# SCH_PoC_Sensor_Jao.net
KiCad netlist of a schematic drawn in EasyEDA
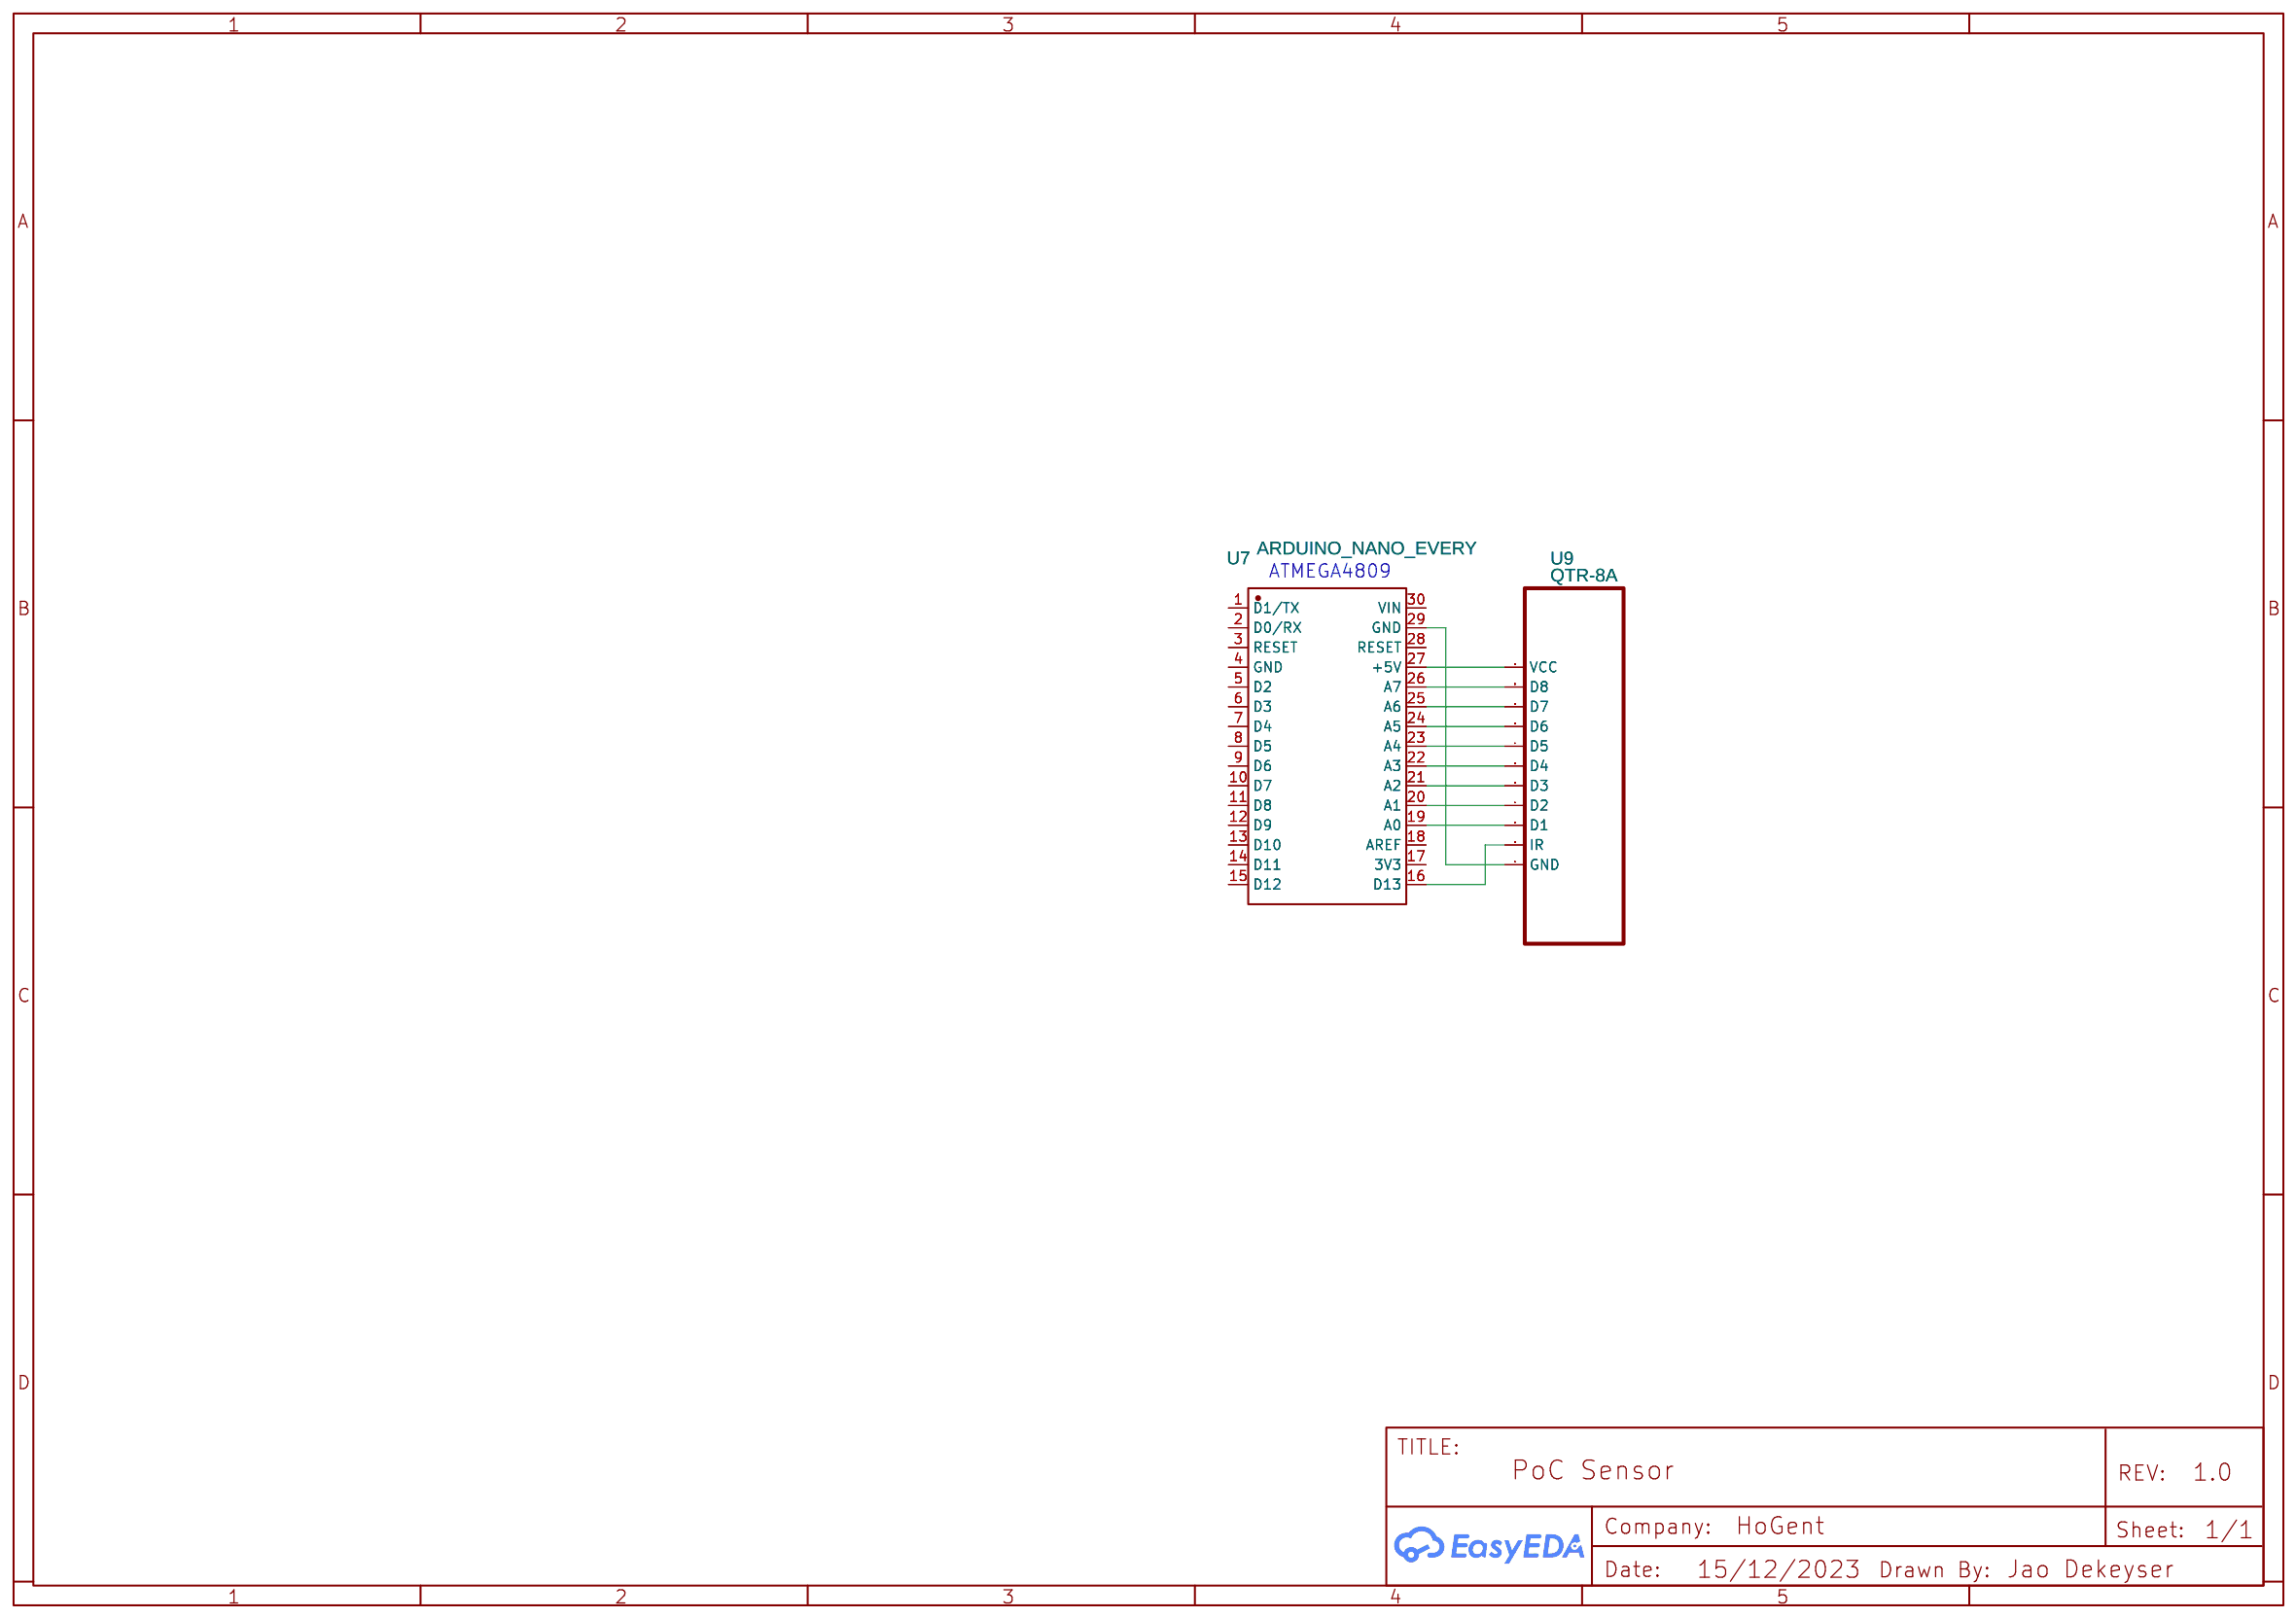
[diagram p0: schematic sheet]

(export (version "E")
  (design (tool "Eeschema 10.0.6"))
  (components
    (comp (ref "U7")
      (value "ARDUINO_NANO_EVERY")
      (fields (field (name "Manufacturer Part") "ARDUINO_NANO"))
      (libsource (lib "") (part "ARDUINO_NANO"))
    )
    (comp (ref "U9") (value "QTR-8A") (libsource (lib "") (part "QTR-8A")))
  )
  (nets
    (net (code "1") (name "Net-(U7-+5V)") (class "Default")
      (node (ref "U7") (pin "27") (pinfunction "+5V_27") (pintype "unspecified"))
      (node (ref "U9") (pin "11") (pinfunction "VCC_11") (pintype "unspecified"))
    )
    (net (code "2") (name "Net-(U7-A0)") (class "Default")
      (node (ref "U7") (pin "19") (pinfunction "A0_19") (pintype "unspecified"))
      (node (ref "U9") (pin "3") (pinfunction "D1_3") (pintype "unspecified"))
    )
    (net (code "3") (name "Net-(U7-A1)") (class "Default")
      (node (ref "U7") (pin "20") (pinfunction "A1_20") (pintype "unspecified"))
      (node (ref "U9") (pin "4") (pinfunction "D2_4") (pintype "unspecified"))
    )
    (net (code "4") (name "Net-(U7-A2)") (class "Default")
      (node (ref "U7") (pin "21") (pinfunction "A2_21") (pintype "unspecified"))
      (node (ref "U9") (pin "5") (pinfunction "D3_5") (pintype "unspecified"))
    )
    (net (code "5") (name "Net-(U7-A3)") (class "Default")
      (node (ref "U7") (pin "22") (pinfunction "A3_22") (pintype "unspecified"))
      (node (ref "U9") (pin "6") (pinfunction "D4_6") (pintype "unspecified"))
    )
    (net (code "6") (name "Net-(U7-A4)") (class "Default")
      (node (ref "U7") (pin "23") (pinfunction "A4_23") (pintype "unspecified"))
      (node (ref "U9") (pin "7") (pinfunction "D5_7") (pintype "unspecified"))
    )
    (net (code "7") (name "Net-(U7-A5)") (class "Default")
      (node (ref "U7") (pin "24") (pinfunction "A5_24") (pintype "unspecified"))
      (node (ref "U9") (pin "8") (pinfunction "D6_8") (pintype "unspecified"))
    )
    (net (code "8") (name "Net-(U7-A6)") (class "Default")
      (node (ref "U7") (pin "25") (pinfunction "A6_25") (pintype "unspecified"))
      (node (ref "U9") (pin "9") (pinfunction "D7_9") (pintype "unspecified"))
    )
    (net (code "9") (name "Net-(U7-A7)") (class "Default")
      (node (ref "U7") (pin "26") (pinfunction "A7_26") (pintype "unspecified"))
      (node (ref "U9") (pin "10") (pinfunction "D8_10") (pintype "unspecified"))
    )
    (net (code "10") (name "Net-(U7-D13)") (class "Default")
      (node (ref "U7") (pin "16") (pinfunction "D13_16") (pintype "unspecified"))
      (node (ref "U9") (pin "2") (pinfunction "IR_2") (pintype "unspecified"))
    )
    (net (code "11") (name "Net-(U9-GND)") (class "Default")
      (node (ref "U7") (pin "29") (pinfunction "GND_29") (pintype "unspecified"))
      (node (ref "U9") (pin "1") (pinfunction "GND_1") (pintype "unspecified"))
    )
    (net (code "12") (name "unconnected-(U7-3V3-Pad17)") (class "Default")
      (node (ref "U7") (pin "17") (pinfunction "3V3_17") (pintype "unspecified"))
    )
    (net (code "13") (name "unconnected-(U7-AREF-Pad18)") (class "Default")
      (node (ref "U7") (pin "18") (pinfunction "AREF_18") (pintype "unspecified"))
    )
    (net (code "14") (name "unconnected-(U7-D0{slash}RX-Pad2)") (class "Default")
      (node (ref "U7") (pin "2") (pinfunction "D0/RX_2") (pintype "unspecified"))
    )
    (net (code "15") (name "unconnected-(U7-D1{slash}TX-Pad1)") (class "Default")
      (node (ref "U7") (pin "1") (pinfunction "D1/TX_1") (pintype "unspecified"))
    )
    (net (code "16") (name "unconnected-(U7-D2-Pad5)") (class "Default")
      (node (ref "U7") (pin "5") (pinfunction "D2_5") (pintype "unspecified"))
    )
    (net (code "17") (name "unconnected-(U7-D3-Pad6)") (class "Default")
      (node (ref "U7") (pin "6") (pinfunction "D3_6") (pintype "unspecified"))
    )
    (net (code "18") (name "unconnected-(U7-D4-Pad7)") (class "Default")
      (node (ref "U7") (pin "7") (pinfunction "D4_7") (pintype "unspecified"))
    )
    (net (code "19") (name "unconnected-(U7-D5-Pad8)") (class "Default")
      (node (ref "U7") (pin "8") (pinfunction "D5_8") (pintype "unspecified"))
    )
    (net (code "20") (name "unconnected-(U7-D6-Pad9)") (class "Default")
      (node (ref "U7") (pin "9") (pinfunction "D6_9") (pintype "unspecified"))
    )
    (net (code "21") (name "unconnected-(U7-D7-Pad10)") (class "Default")
      (node (ref "U7") (pin "10") (pinfunction "D7_10") (pintype "unspecified"))
    )
    (net (code "22") (name "unconnected-(U7-D8-Pad11)") (class "Default")
      (node (ref "U7") (pin "11") (pinfunction "D8_11") (pintype "unspecified"))
    )
    (net (code "23") (name "unconnected-(U7-D9-Pad12)") (class "Default")
      (node (ref "U7") (pin "12") (pinfunction "D9_12") (pintype "unspecified"))
    )
    (net (code "24") (name "unconnected-(U7-D10-Pad13)") (class "Default")
      (node (ref "U7") (pin "13") (pinfunction "D10_13") (pintype "unspecified"))
    )
    (net (code "25") (name "unconnected-(U7-D11-Pad14)") (class "Default")
      (node (ref "U7") (pin "14") (pinfunction "D11_14") (pintype "unspecified"))
    )
    (net (code "26") (name "unconnected-(U7-D12-Pad15)") (class "Default")
      (node (ref "U7") (pin "15") (pinfunction "D12_15") (pintype "unspecified"))
    )
    (net (code "27") (name "unconnected-(U7-GND-Pad4)") (class "Default")
      (node (ref "U7") (pin "4") (pinfunction "GND_4") (pintype "unspecified"))
    )
    (net (code "28") (name "unconnected-(U7-RESET-Pad3)") (class "Default")
      (node (ref "U7") (pin "3") (pinfunction "RESET_3") (pintype "unspecified"))
    )
    (net (code "29") (name "unconnected-(U7-RESET-Pad28)") (class "Default")
      (node (ref "U7") (pin "28") (pinfunction "RESET_28") (pintype "unspecified"))
    )
    (net (code "30") (name "unconnected-(U7-VIN-Pad30)") (class "Default")
      (node (ref "U7") (pin "30") (pinfunction "VIN_30") (pintype "unspecified"))
    )
  )
)
